# design.net
KiCad netlist of a schematic drawn in EasyEDA Pro
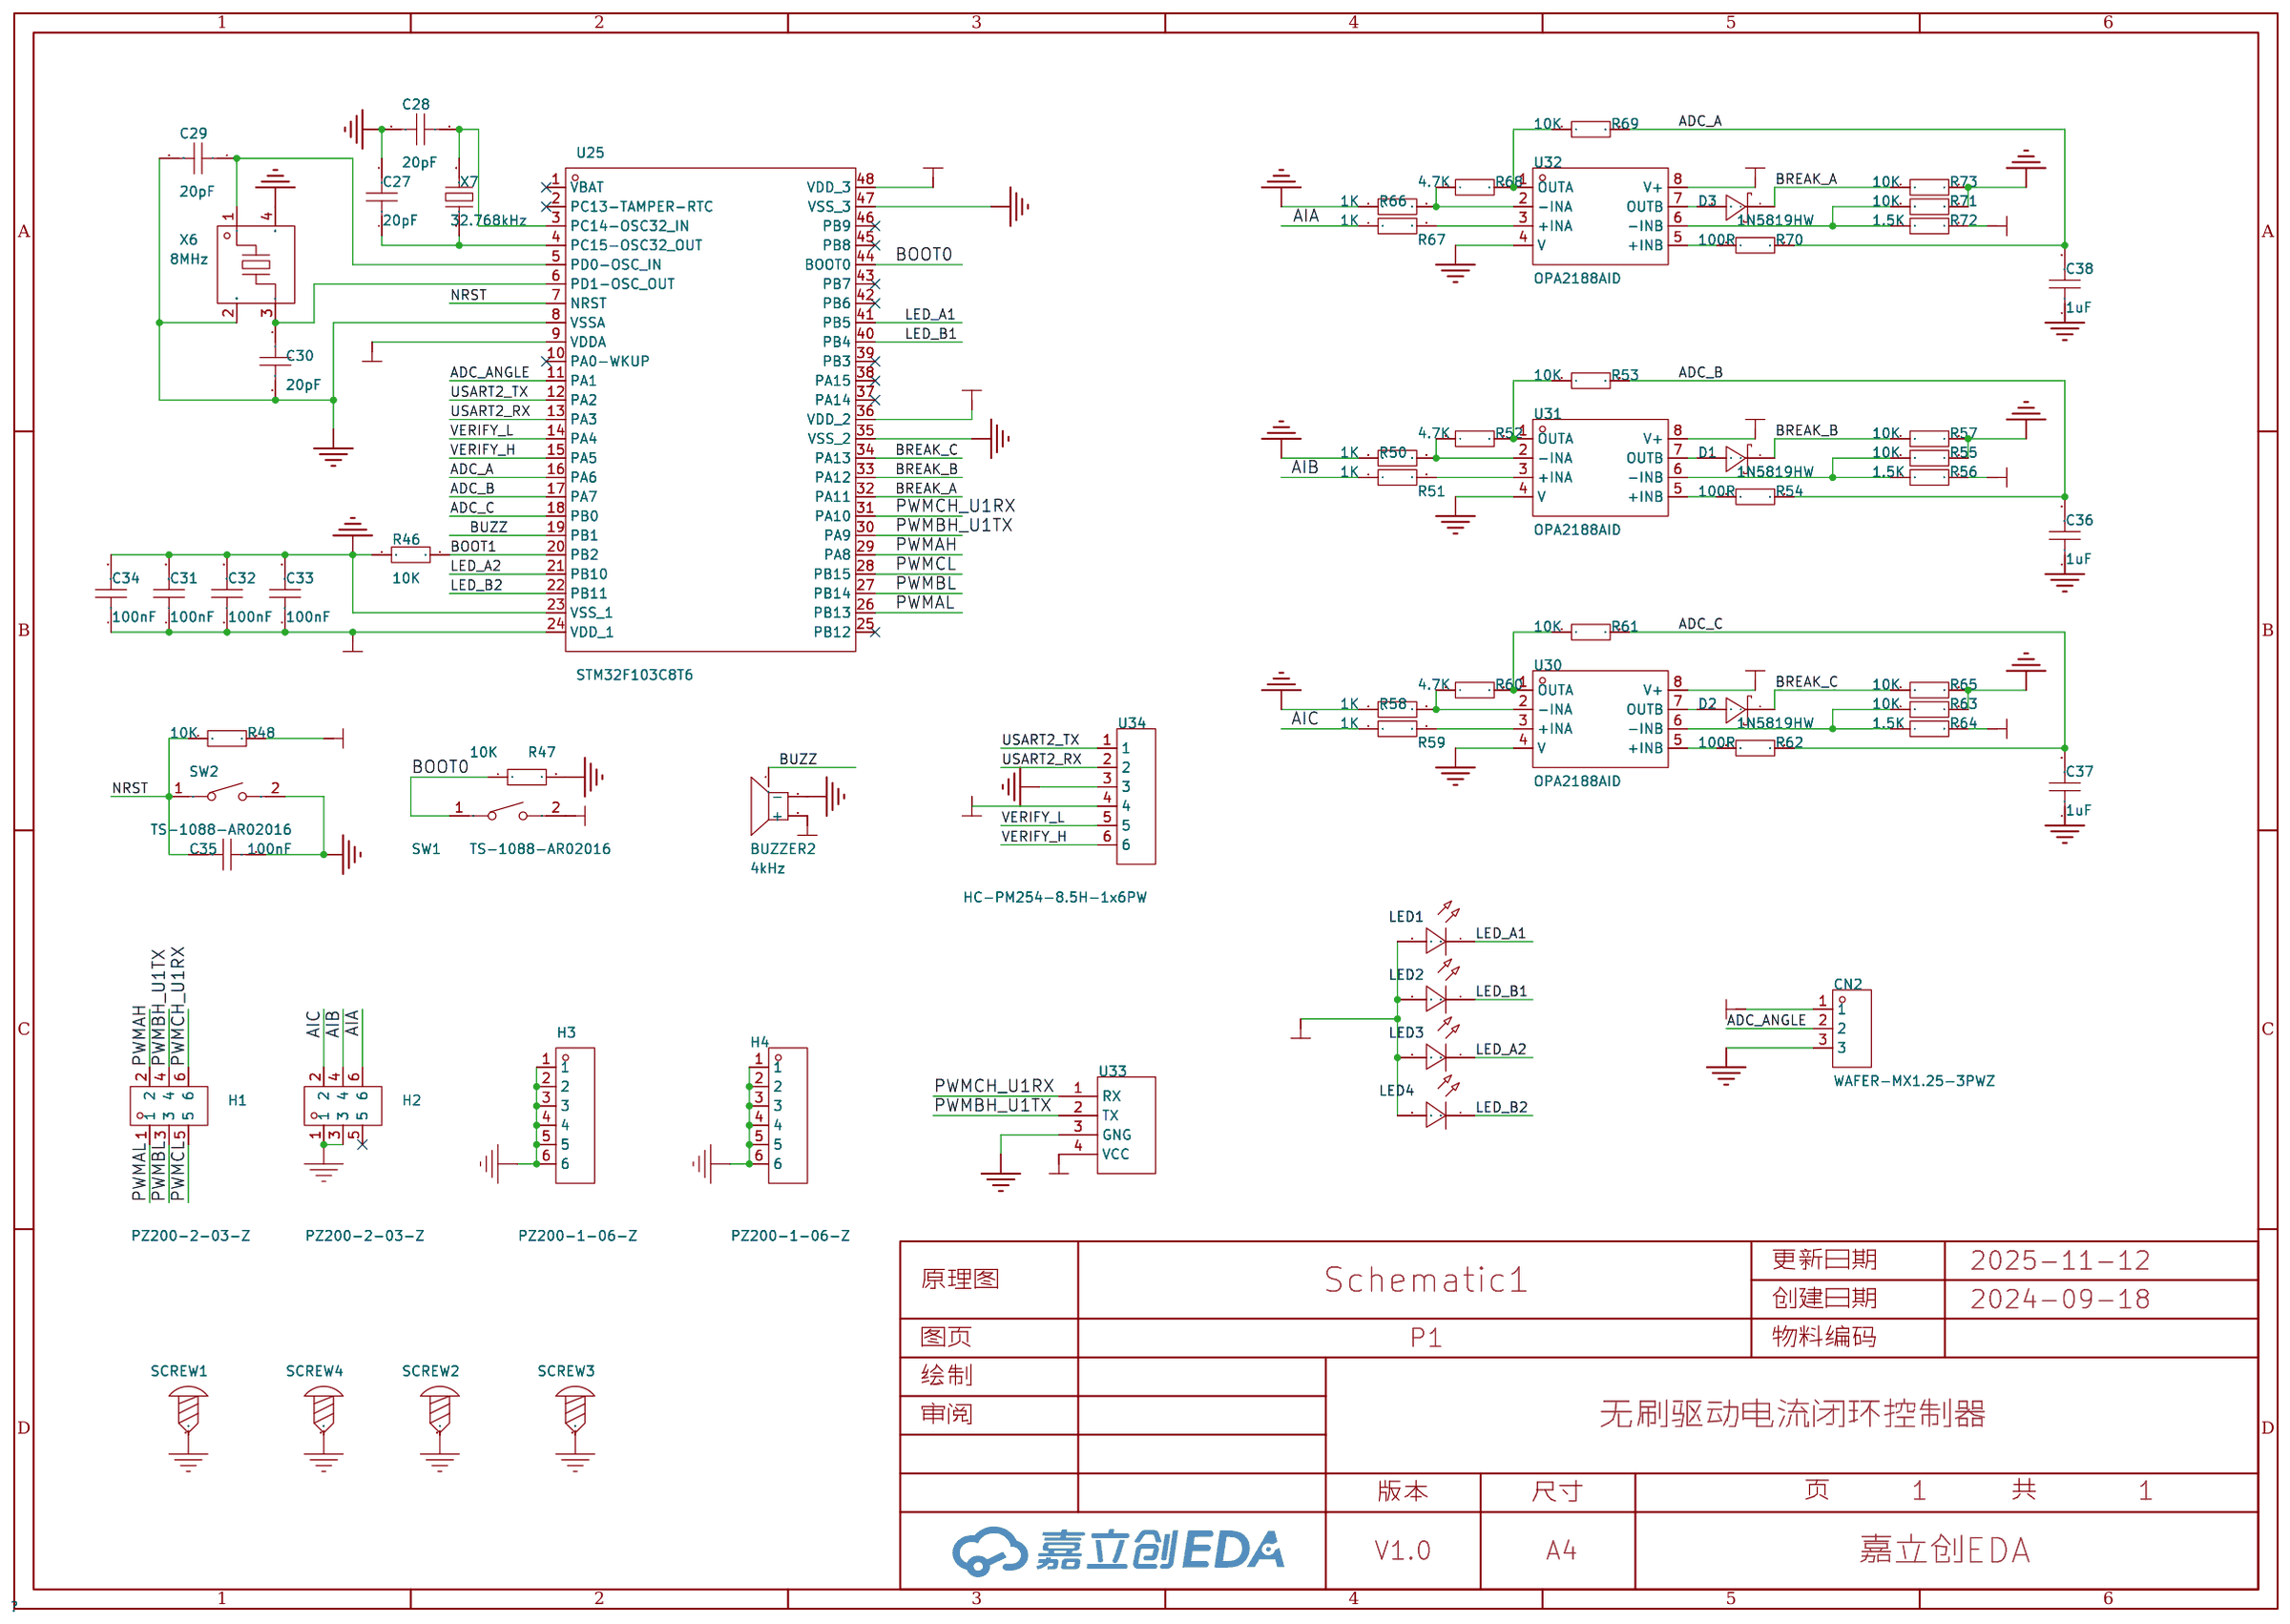
[diagram p0: schematic sheet]

(export (version "E")
  (design (tool "Eeschema 10.0.6"))
  (components
    (comp (ref "BUZZER2")
      (value "4kHz")
      (footprint "easyedapro:BUZ-SMD_L5.0-W5.5-P4.60")
      (description "驱动方式:无源(外部驱动);构造类型:电磁式;频率:4kHz;")
      (fields (field (name "Manufacturer Part") "MLT-5020") (field (name "Manufacturer") "华能"))
      (libsource (lib "easyedapro") (part "MLT-5020"))
    )
    (comp (ref "C27")
      (value "20pF")
      (footprint "easyedapro:C0402")
      (libsource (lib "easyedapro") (part "CapAcitance"))
    )
    (comp (ref "C28")
      (value "20pF")
      (footprint "easyedapro:C0402")
      (libsource (lib "easyedapro") (part "CapAcitance"))
    )
    (comp (ref "C29")
      (value "20pF")
      (footprint "easyedapro:C0402")
      (libsource (lib "easyedapro") (part "CapAcitance"))
    )
    (comp (ref "C30")
      (value "20pF")
      (footprint "easyedapro:C0402")
      (libsource (lib "easyedapro") (part "CapAcitance"))
    )
    (comp (ref "C31")
      (value "100nF")
      (footprint "easyedapro:C0402")
      (libsource (lib "easyedapro") (part "CapAcitance"))
    )
    (comp (ref "C32")
      (value "100nF")
      (footprint "easyedapro:C0402")
      (libsource (lib "easyedapro") (part "CapAcitance"))
    )
    (comp (ref "C33")
      (value "100nF")
      (footprint "easyedapro:C0402")
      (libsource (lib "easyedapro") (part "CapAcitance"))
    )
    (comp (ref "C34")
      (value "100nF")
      (footprint "easyedapro:C0402")
      (libsource (lib "easyedapro") (part "CapAcitance"))
    )
    (comp (ref "C35")
      (value "100nF")
      (footprint "easyedapro:C0402")
      (libsource (lib "easyedapro") (part "CapAcitance"))
    )
    (comp (ref "C36")
      (value "1uF")
      (footprint "easyedapro:C0402")
      (libsource (lib "easyedapro") (part "CapAcitance"))
    )
    (comp (ref "C37")
      (value "1uF")
      (footprint "easyedapro:C0402")
      (libsource (lib "easyedapro") (part "CapAcitance"))
    )
    (comp (ref "C38")
      (value "1uF")
      (footprint "easyedapro:C0402")
      (libsource (lib "easyedapro") (part "CapAcitance"))
    )
    (comp (ref "CN2")
      (value "WAFER-MX1.25-3PWZ")
      (footprint "easyedapro:CONN-TH_3P-P1.25_XUNPU_WAFER-MX1.25-3PWZ")
      (description "间距:1.25mm;插针结构:1x3P;排数:1;每排PIN数:3;公母:公型插针;安装方式:弯插;额定电流:1A;工作温度范围:-25°C~+85°C;")
      (fields (field (name "Manufacturer") "XUNPU(讯普)"))
      (libsource (lib "easyedapro") (part "WAFER-MX1.25-3PWZ"))
    )
    (comp (ref "D1")
      (value "1N5819HW")
      (footprint "easyedapro:SOD-123_L2.7-W1.6-LS3.7-RD")
      (description "正向压降(Vf):450mV@1A;直流反向耐压(Vr):40V;整流电流:1A;")
      (fields (field (name "Manufacturer") "DIODES(美台)"))
      (libsource (lib "easyedapro") (part "1N5819HW-7-F"))
    )
    (comp (ref "D2")
      (value "1N5819HW")
      (footprint "easyedapro:SOD-123_L2.7-W1.6-LS3.7-RD")
      (description "正向压降(Vf):450mV@1A;直流反向耐压(Vr):40V;整流电流:1A;")
      (fields (field (name "Manufacturer") "DIODES(美台)"))
      (libsource (lib "easyedapro") (part "1N5819HW-7-F"))
    )
    (comp (ref "D3")
      (value "1N5819HW")
      (footprint "easyedapro:SOD-123_L2.7-W1.6-LS3.7-RD")
      (description "正向压降(Vf):450mV@1A;直流反向耐压(Vr):40V;整流电流:1A;")
      (fields (field (name "Manufacturer") "DIODES(美台)"))
      (libsource (lib "easyedapro") (part "1N5819HW-7-F"))
    )
    (comp (ref "H1")
      (value "PZ200-2-03-Z")
      (footprint "easyedapro:HDR-TH_6P-P2.00-V-M-R2-C3-S2.00")
      (fields (field (name "Manufacturer") "HCTL(华灿天禄)"))
      (libsource (lib "easyedapro") (part "PZ200-2-03-Z"))
    )
    (comp (ref "H2")
      (value "PZ200-2-03-Z")
      (footprint "easyedapro:HDR-TH_6P-P2.00-V-M-R2-C3-S2.00")
      (fields (field (name "Manufacturer") "HCTL(华灿天禄)"))
      (libsource (lib "easyedapro") (part "PZ200-2-03-Z"))
    )
    (comp (ref "H3")
      (value "PZ200-1-06-Z")
      (footprint "easyedapro:HDR-TH_6P-P2.00-V-M")
      (fields (field (name "Manufacturer") "HCTL(华灿天禄)"))
      (libsource (lib "easyedapro") (part "PZ200-1-06-Z"))
    )
    (comp (ref "H4")
      (value "PZ200-1-06-Z")
      (footprint "easyedapro:HDR-TH_6P-P2.00-V-M")
      (fields (field (name "Manufacturer") "HCTL(华灿天禄)"))
      (libsource (lib "easyedapro") (part "PZ200-1-06-Z"))
    )
    (comp (ref "LED1")
      (value "~")
      (footprint "easyedapro:LED_0402")
      (libsource (lib "easyedapro") (part "LED_G"))
    )
    (comp (ref "LED2")
      (value "~")
      (footprint "easyedapro:LED_0402")
      (libsource (lib "easyedapro") (part "LED_G"))
    )
    (comp (ref "LED3")
      (value "~")
      (footprint "easyedapro:LED_0402")
      (libsource (lib "easyedapro") (part "LED_G"))
    )
    (comp (ref "LED4")
      (value "~")
      (footprint "easyedapro:LED_0402")
      (libsource (lib "easyedapro") (part "LED_G"))
    )
    (comp (ref "R46") (value "10K") (footprint "easyedapro:R0402") (libsource (lib "easyedapro") (part "电阻")))
    (comp (ref "R47") (value "10K") (footprint "easyedapro:R0402") (libsource (lib "easyedapro") (part "电阻")))
    (comp (ref "R48") (value "10K") (footprint "easyedapro:R0402") (libsource (lib "easyedapro") (part "电阻")))
    (comp (ref "R50") (value "1K") (footprint "easyedapro:R0402") (libsource (lib "easyedapro") (part "电阻")))
    (comp (ref "R51") (value "1K") (footprint "easyedapro:R0402") (libsource (lib "easyedapro") (part "电阻")))
    (comp (ref "R52")
      (value "4.7K")
      (footprint "easyedapro:R0402")
      (libsource (lib "easyedapro") (part "电阻"))
    )
    (comp (ref "R53") (value "10K") (footprint "easyedapro:R0402") (libsource (lib "easyedapro") (part "电阻")))
    (comp (ref "R54")
      (value "100R")
      (footprint "easyedapro:R0402")
      (libsource (lib "easyedapro") (part "电阻"))
    )
    (comp (ref "R55") (value "10K") (footprint "easyedapro:R0402") (libsource (lib "easyedapro") (part "电阻")))
    (comp (ref "R56")
      (value "1.5K")
      (footprint "easyedapro:R0402")
      (libsource (lib "easyedapro") (part "电阻"))
    )
    (comp (ref "R57") (value "10K") (footprint "easyedapro:R0402") (libsource (lib "easyedapro") (part "电阻")))
    (comp (ref "R58") (value "1K") (footprint "easyedapro:R0402") (libsource (lib "easyedapro") (part "电阻")))
    (comp (ref "R59") (value "1K") (footprint "easyedapro:R0402") (libsource (lib "easyedapro") (part "电阻")))
    (comp (ref "R60")
      (value "4.7K")
      (footprint "easyedapro:R0402")
      (libsource (lib "easyedapro") (part "电阻"))
    )
    (comp (ref "R61") (value "10K") (footprint "easyedapro:R0402") (libsource (lib "easyedapro") (part "电阻")))
    (comp (ref "R62")
      (value "100R")
      (footprint "easyedapro:R0402")
      (libsource (lib "easyedapro") (part "电阻"))
    )
    (comp (ref "R63") (value "10K") (footprint "easyedapro:R0402") (libsource (lib "easyedapro") (part "电阻")))
    (comp (ref "R64")
      (value "1.5K")
      (footprint "easyedapro:R0402")
      (libsource (lib "easyedapro") (part "电阻"))
    )
    (comp (ref "R65") (value "10K") (footprint "easyedapro:R0402") (libsource (lib "easyedapro") (part "电阻")))
    (comp (ref "R66") (value "1K") (footprint "easyedapro:R0402") (libsource (lib "easyedapro") (part "电阻")))
    (comp (ref "R67") (value "1K") (footprint "easyedapro:R0402") (libsource (lib "easyedapro") (part "电阻")))
    (comp (ref "R68")
      (value "4.7K")
      (footprint "easyedapro:R0402")
      (libsource (lib "easyedapro") (part "电阻"))
    )
    (comp (ref "R69") (value "10K") (footprint "easyedapro:R0402") (libsource (lib "easyedapro") (part "电阻")))
    (comp (ref "R70")
      (value "100R")
      (footprint "easyedapro:R0402")
      (libsource (lib "easyedapro") (part "电阻"))
    )
    (comp (ref "R71") (value "10K") (footprint "easyedapro:R0402") (libsource (lib "easyedapro") (part "电阻")))
    (comp (ref "R72")
      (value "1.5K")
      (footprint "easyedapro:R0402")
      (libsource (lib "easyedapro") (part "电阻"))
    )
    (comp (ref "R73") (value "10K") (footprint "easyedapro:R0402") (libsource (lib "easyedapro") (part "电阻")))
    (comp (ref "SCREW1")
      (value "~")
      (footprint "easyedapro:M3螺丝")
      (libsource (lib "easyedapro") (part "螺丝孔"))
    )
    (comp (ref "SCREW2")
      (value "~")
      (footprint "easyedapro:M3螺丝")
      (libsource (lib "easyedapro") (part "螺丝孔"))
    )
    (comp (ref "SCREW3")
      (value "~")
      (footprint "easyedapro:M3螺丝")
      (libsource (lib "easyedapro") (part "螺丝孔"))
    )
    (comp (ref "SCREW4")
      (value "~")
      (footprint "easyedapro:M3螺丝")
      (libsource (lib "easyedapro") (part "螺丝孔"))
    )
    (comp (ref "SW1")
      (value "TS-1088-AR02016")
      (footprint "easyedapro:SW-SMD_L3.9-W3.0-P4.45")
      (fields (field (name "Manufacturer") "XUNPU(讯普)"))
      (libsource (lib "easyedapro") (part "TS-1088-AR02016"))
    )
    (comp (ref "SW2")
      (value "TS-1088-AR02016")
      (footprint "easyedapro:SW-SMD_L3.9-W3.0-P4.45")
      (fields (field (name "Manufacturer") "XUNPU(讯普)"))
      (libsource (lib "easyedapro") (part "TS-1088-AR02016"))
    )
    (comp (ref "U25")
      (value "STM32F103C8T6")
      (footprint "easyedapro:LQFP-48_L7.0-W7.0-P0.50-LS9.0-BL")
      (description "CPU内核:ARM-M3;CPU最大主频:72MHz;应用领域:-;")
      (fields (field (name "Manufacturer") "ST(意法半导体)"))
      (libsource (lib "easyedapro") (part "STM32F103C8T6"))
    )
    (comp (ref "U30")
      (value "OPA2188AID")
      (footprint "easyedapro:SOIC-8_L4.9-W3.9-P1.27-LS6.0-BL")
      (description "放大器数:双路;增益带宽积(GBP):2MHz;输入偏置电流(Ib):160pA;输入失调电压(Vos):6uV;压摆率(SR):0.8V/us;带宽(-3db):-;轨到轨:-;")
      (fields (field (name "Manufacturer") "TI(德州仪器)"))
      (libsource (lib "easyedapro") (part "OPA2188AID"))
    )
    (comp (ref "U31")
      (value "OPA2188AID")
      (footprint "easyedapro:SOIC-8_L4.9-W3.9-P1.27-LS6.0-BL")
      (description "放大器数:双路;增益带宽积(GBP):2MHz;输入偏置电流(Ib):160pA;输入失调电压(Vos):6uV;压摆率(SR):0.8V/us;带宽(-3db):-;轨到轨:-;")
      (fields (field (name "Manufacturer") "TI(德州仪器)"))
      (libsource (lib "easyedapro") (part "OPA2188AID"))
    )
    (comp (ref "U32")
      (value "OPA2188AID")
      (footprint "easyedapro:SOIC-8_L4.9-W3.9-P1.27-LS6.0-BL")
      (description "放大器数:双路;增益带宽积(GBP):2MHz;输入偏置电流(Ib):160pA;输入失调电压(Vos):6uV;压摆率(SR):0.8V/us;带宽(-3db):-;轨到轨:-;")
      (fields (field (name "Manufacturer") "TI(德州仪器)"))
      (libsource (lib "easyedapro") (part "OPA2188AID"))
    )
    (comp (ref "U33")
      (value "~")
      (footprint "easyedapro:2.54串口烧录接口")
      (libsource (lib "easyedapro") (part "2.54串口烧录接口"))
    )
    (comp (ref "U34")
      (value "HC-PM254-8.5H-1x6PW")
      (footprint "easyedapro:HDR-TH_HC-PM254-8.5H-1X6PW")
      (fields (field (name "Manufacturer") "HC(虹成电子)"))
      (libsource (lib "easyedapro") (part "HC-PM254-8.5H-1X6PW"))
    )
    (comp (ref "X6")
      (value "8MHz")
      (footprint "easyedapro:OSC-SMD_4P-L3.2-W2.5-BL")
      (description "晶振类型:贴片无源晶振;频率:8MHz;常温频差:±10ppm;负载电容:12pF;频率稳定度(全温):±30ppm;")
      (fields (field (name "Manufacturer Part") "X32258MOB4SI") (field (name "Manufacturer") "YXC(扬兴晶振)"))
      (libsource (lib "easyedapro") (part "X32258MOB4SI"))
    )
    (comp (ref "X7")
      (value "32.768kHz")
      (footprint "easyedapro:OSC-SMD_L3.2-W1.5")
      (description "频率:32.768kHz;负载电容:12.5pF;频率公差:±20ppm;")
      (fields (field (name "Manufacturer Part") "X321532768KGD2SI") (field (name "Manufacturer") "YXC(扬兴晶振)"))
      (libsource (lib "easyedapro") (part "X321532768KGD2SI"))
    )
  )
  (nets
    (net (code "1") (name "/ADC_A") (class "Default")
      (node (ref "C38") (pin "2") (pinfunction "2_2") (pintype "input"))
      (node (ref "R69") (pin "2") (pinfunction "2_2") (pintype "input"))
      (node (ref "R70") (pin "2") (pinfunction "2_2") (pintype "input"))
      (node (ref "U25") (pin "16") (pinfunction "PA6_16") (pintype "unspecified"))
    )
    (net (code "2") (name "/ADC_ANGLE") (class "Default")
      (node (ref "CN2") (pin "2") (pinfunction "2_2") (pintype "input"))
      (node (ref "U25") (pin "11") (pinfunction "PA1_11") (pintype "unspecified"))
    )
    (net (code "3") (name "/ADC_B") (class "Default")
      (node (ref "C36") (pin "2") (pinfunction "2_2") (pintype "input"))
      (node (ref "R53") (pin "2") (pinfunction "2_2") (pintype "input"))
      (node (ref "R54") (pin "2") (pinfunction "2_2") (pintype "input"))
      (node (ref "U25") (pin "17") (pinfunction "PA7_17") (pintype "unspecified"))
    )
    (net (code "4") (name "/ADC_C") (class "Default")
      (node (ref "C37") (pin "2") (pinfunction "2_2") (pintype "input"))
      (node (ref "R61") (pin "2") (pinfunction "2_2") (pintype "input"))
      (node (ref "R62") (pin "2") (pinfunction "2_2") (pintype "input"))
      (node (ref "U25") (pin "18") (pinfunction "PB0_18") (pintype "unspecified"))
    )
    (net (code "5") (name "/AIA") (class "Default")
      (node (ref "H2") (pin "6") (pinfunction "6_6") (pintype "unspecified"))
      (node (ref "R67") (pin "1") (pinfunction "1_1") (pintype "input"))
    )
    (net (code "6") (name "/AIB") (class "Default")
      (node (ref "H2") (pin "4") (pinfunction "4_4") (pintype "unspecified"))
      (node (ref "R51") (pin "1") (pinfunction "1_1") (pintype "input"))
    )
    (net (code "7") (name "/AIC") (class "Default")
      (node (ref "H2") (pin "2") (pinfunction "2_2") (pintype "unspecified"))
      (node (ref "R59") (pin "1") (pinfunction "1_1") (pintype "input"))
    )
    (net (code "8") (name "/BOOT0") (class "Default")
      (node (ref "R47") (pin "1") (pinfunction "1_1") (pintype "input"))
      (node (ref "SW1") (pin "1") (pinfunction "1_1") (pintype "unspecified"))
      (node (ref "U25") (pin "44") (pinfunction "BOOT0_44") (pintype "unspecified"))
    )
    (net (code "9") (name "/BOOT1") (class "Default")
      (node (ref "R46") (pin "1") (pinfunction "1_1") (pintype "input"))
      (node (ref "U25") (pin "20") (pinfunction "PB2_20") (pintype "unspecified"))
    )
    (net (code "10") (name "/BREAK_A") (class "Default")
      (node (ref "D3") (pin "1") (pinfunction "K_1") (pintype "unspecified"))
      (node (ref "R73") (pin "1") (pinfunction "1_1") (pintype "input"))
      (node (ref "U25") (pin "32") (pinfunction "PA11_32") (pintype "unspecified"))
    )
    (net (code "11") (name "/BREAK_B") (class "Default")
      (node (ref "D1") (pin "1") (pinfunction "K_1") (pintype "unspecified"))
      (node (ref "R57") (pin "1") (pinfunction "1_1") (pintype "input"))
      (node (ref "U25") (pin "33") (pinfunction "PA12_33") (pintype "unspecified"))
    )
    (net (code "12") (name "/BREAK_C") (class "Default")
      (node (ref "D2") (pin "1") (pinfunction "K_1") (pintype "unspecified"))
      (node (ref "R65") (pin "1") (pinfunction "1_1") (pintype "input"))
      (node (ref "U25") (pin "34") (pinfunction "PA13_34") (pintype "unspecified"))
    )
    (net (code "13") (name "/BUZZ") (class "Default")
      (node (ref "BUZZER2") (pin "3") (pinfunction "NC_3") (pintype "unspecified"))
      (node (ref "U25") (pin "19") (pinfunction "PB1_19") (pintype "unspecified"))
    )
    (net (code "14") (name "/LED_A1") (class "Default")
      (node (ref "LED1") (pin "1") (pinfunction "C_1") (pintype "input"))
      (node (ref "U25") (pin "41") (pinfunction "PB5_41") (pintype "unspecified"))
    )
    (net (code "15") (name "/LED_A2") (class "Default")
      (node (ref "LED3") (pin "1") (pinfunction "C_1") (pintype "input"))
      (node (ref "U25") (pin "21") (pinfunction "PB10_21") (pintype "unspecified"))
    )
    (net (code "16") (name "/LED_B1") (class "Default")
      (node (ref "LED2") (pin "1") (pinfunction "C_1") (pintype "input"))
      (node (ref "U25") (pin "40") (pinfunction "PB4_40") (pintype "unspecified"))
    )
    (net (code "17") (name "/LED_B2") (class "Default")
      (node (ref "LED4") (pin "1") (pinfunction "C_1") (pintype "input"))
      (node (ref "U25") (pin "22") (pinfunction "PB11_22") (pintype "unspecified"))
    )
    (net (code "18") (name "/NRST") (class "Default")
      (node (ref "C35") (pin "1") (pinfunction "1_1") (pintype "input"))
      (node (ref "R48") (pin "1") (pinfunction "1_1") (pintype "input"))
      (node (ref "SW2") (pin "1") (pinfunction "1_1") (pintype "unspecified"))
      (node (ref "U25") (pin "7") (pinfunction "NRST_7") (pintype "unspecified"))
    )
    (net (code "19") (name "/PWMAH") (class "Default")
      (node (ref "H1") (pin "2") (pinfunction "2_2") (pintype "unspecified"))
      (node (ref "U25") (pin "29") (pinfunction "PA8_29") (pintype "unspecified"))
    )
    (net (code "20") (name "/PWMAL") (class "Default")
      (node (ref "H1") (pin "1") (pinfunction "1_1") (pintype "unspecified"))
      (node (ref "U25") (pin "26") (pinfunction "PB13_26") (pintype "unspecified"))
    )
    (net (code "21") (name "/PWMBH_U1TX") (class "Default")
      (node (ref "H1") (pin "4") (pinfunction "4_4") (pintype "unspecified"))
      (node (ref "U25") (pin "30") (pinfunction "PA9_30") (pintype "unspecified"))
      (node (ref "U33") (pin "2") (pinfunction "TX_2") (pintype "input"))
    )
    (net (code "22") (name "/PWMBL") (class "Default")
      (node (ref "H1") (pin "3") (pinfunction "3_3") (pintype "unspecified"))
      (node (ref "U25") (pin "27") (pinfunction "PB14_27") (pintype "unspecified"))
    )
    (net (code "23") (name "/PWMCH_U1RX") (class "Default")
      (node (ref "H1") (pin "6") (pinfunction "6_6") (pintype "unspecified"))
      (node (ref "U25") (pin "31") (pinfunction "PA10_31") (pintype "unspecified"))
      (node (ref "U33") (pin "1") (pinfunction "RX_1") (pintype "input"))
    )
    (net (code "24") (name "/PWMCL") (class "Default")
      (node (ref "H1") (pin "5") (pinfunction "5_5") (pintype "unspecified"))
      (node (ref "U25") (pin "28") (pinfunction "PB15_28") (pintype "unspecified"))
    )
    (net (code "25") (name "/USART2_RX") (class "Default")
      (node (ref "U25") (pin "13") (pinfunction "PA3_13") (pintype "unspecified"))
      (node (ref "U34") (pin "2") (pinfunction "2_2") (pintype "unspecified"))
    )
    (net (code "26") (name "/USART2_TX") (class "Default")
      (node (ref "U25") (pin "12") (pinfunction "PA2_12") (pintype "unspecified"))
      (node (ref "U34") (pin "1") (pinfunction "1_1") (pintype "unspecified"))
    )
    (net (code "27") (name "/VERIFY_H") (class "Default")
      (node (ref "U25") (pin "15") (pinfunction "PA5_15") (pintype "unspecified"))
      (node (ref "U34") (pin "6") (pinfunction "6_6") (pintype "unspecified"))
    )
    (net (code "28") (name "/VERIFY_L") (class "Default")
      (node (ref "U25") (pin "14") (pinfunction "PA4_14") (pintype "unspecified"))
      (node (ref "U34") (pin "5") (pinfunction "5_5") (pintype "unspecified"))
    )
    (net (code "29") (name "3V3") (class "Default")
      (node (ref "BUZZER2") (pin "1") (pinfunction "+_1") (pintype "unspecified"))
      (node (ref "C31") (pin "1") (pinfunction "1_1") (pintype "input"))
      (node (ref "C32") (pin "1") (pinfunction "1_1") (pintype "input"))
      (node (ref "C33") (pin "1") (pinfunction "1_1") (pintype "input"))
      (node (ref "C34") (pin "1") (pinfunction "1_1") (pintype "input"))
      (node (ref "CN2") (pin "1") (pinfunction "1_1") (pintype "input"))
      (node (ref "LED1") (pin "2") (pinfunction "A_2") (pintype "input"))
      (node (ref "LED2") (pin "2") (pinfunction "A_2") (pintype "input"))
      (node (ref "LED3") (pin "2") (pinfunction "A_2") (pintype "input"))
      (node (ref "LED4") (pin "2") (pinfunction "A_2") (pintype "input"))
      (node (ref "R48") (pin "2") (pinfunction "2_2") (pintype "input"))
      (node (ref "R56") (pin "2") (pinfunction "2_2") (pintype "input"))
      (node (ref "R64") (pin "2") (pinfunction "2_2") (pintype "input"))
      (node (ref "R72") (pin "2") (pinfunction "2_2") (pintype "input"))
      (node (ref "SW1") (pin "2") (pinfunction "2_2") (pintype "unspecified"))
      (node (ref "U25") (pin "24") (pinfunction "VDD_1_24") (pintype "unspecified"))
      (node (ref "U25") (pin "36") (pinfunction "VDD_2_36") (pintype "unspecified"))
      (node (ref "U25") (pin "48") (pinfunction "VDD_3_48") (pintype "unspecified"))
      (node (ref "U25") (pin "9") (pinfunction "VDDA_9") (pintype "unspecified"))
      (node (ref "U30") (pin "8") (pinfunction "V+_8") (pintype "unspecified"))
      (node (ref "U31") (pin "8") (pinfunction "V+_8") (pintype "unspecified"))
      (node (ref "U32") (pin "8") (pinfunction "V+_8") (pintype "unspecified"))
      (node (ref "U33") (pin "4") (pinfunction "VCC_4") (pintype "input"))
      (node (ref "U34") (pin "4") (pinfunction "4_4") (pintype "unspecified"))
    )
    (net (code "30") (name "GND") (class "Default")
      (node (ref "BUZZER2") (pin "2") (pinfunction "-_2") (pintype "unspecified"))
      (node (ref "C27") (pin "2") (pinfunction "2_2") (pintype "input"))
      (node (ref "C28") (pin "2") (pinfunction "2_2") (pintype "input"))
      (node (ref "C29") (pin "2") (pinfunction "2_2") (pintype "input"))
      (node (ref "C30") (pin "2") (pinfunction "2_2") (pintype "input"))
      (node (ref "C31") (pin "2") (pinfunction "2_2") (pintype "input"))
      (node (ref "C32") (pin "2") (pinfunction "2_2") (pintype "input"))
      (node (ref "C33") (pin "2") (pinfunction "2_2") (pintype "input"))
      (node (ref "C34") (pin "2") (pinfunction "2_2") (pintype "input"))
      (node (ref "C35") (pin "2") (pinfunction "2_2") (pintype "input"))
      (node (ref "C36") (pin "1") (pinfunction "1_1") (pintype "input"))
      (node (ref "C37") (pin "1") (pinfunction "1_1") (pintype "input"))
      (node (ref "C38") (pin "1") (pinfunction "1_1") (pintype "input"))
      (node (ref "CN2") (pin "3") (pinfunction "3_3") (pintype "input"))
      (node (ref "H2") (pin "1") (pinfunction "1_1") (pintype "unspecified"))
      (node (ref "H2") (pin "3") (pinfunction "3_3") (pintype "unspecified"))
      (node (ref "H3") (pin "1") (pinfunction "1_1") (pintype "unspecified"))
      (node (ref "H3") (pin "2") (pinfunction "2_2") (pintype "unspecified"))
      (node (ref "H3") (pin "3") (pinfunction "3_3") (pintype "unspecified"))
      (node (ref "H3") (pin "4") (pinfunction "4_4") (pintype "unspecified"))
      (node (ref "H3") (pin "5") (pinfunction "5_5") (pintype "unspecified"))
      (node (ref "H3") (pin "6") (pinfunction "6_6") (pintype "unspecified"))
      (node (ref "H4") (pin "1") (pinfunction "1_1") (pintype "unspecified"))
      (node (ref "H4") (pin "2") (pinfunction "2_2") (pintype "unspecified"))
      (node (ref "H4") (pin "3") (pinfunction "3_3") (pintype "unspecified"))
      (node (ref "H4") (pin "4") (pinfunction "4_4") (pintype "unspecified"))
      (node (ref "H4") (pin "5") (pinfunction "5_5") (pintype "unspecified"))
      (node (ref "H4") (pin "6") (pinfunction "6_6") (pintype "unspecified"))
      (node (ref "R46") (pin "2") (pinfunction "2_2") (pintype "input"))
      (node (ref "R47") (pin "2") (pinfunction "2_2") (pintype "input"))
      (node (ref "R50") (pin "1") (pinfunction "1_1") (pintype "input"))
      (node (ref "R55") (pin "2") (pinfunction "2_2") (pintype "input"))
      (node (ref "R57") (pin "2") (pinfunction "2_2") (pintype "input"))
      (node (ref "R58") (pin "1") (pinfunction "1_1") (pintype "input"))
      (node (ref "R63") (pin "2") (pinfunction "2_2") (pintype "input"))
      (node (ref "R65") (pin "2") (pinfunction "2_2") (pintype "input"))
      (node (ref "R66") (pin "1") (pinfunction "1_1") (pintype "input"))
      (node (ref "R71") (pin "2") (pinfunction "2_2") (pintype "input"))
      (node (ref "R73") (pin "2") (pinfunction "2_2") (pintype "input"))
      (node (ref "SCREW1") (pin "1") (pinfunction "1_1") (pintype "input"))
      (node (ref "SCREW2") (pin "1") (pinfunction "1_1") (pintype "input"))
      (node (ref "SCREW3") (pin "1") (pinfunction "1_1") (pintype "input"))
      (node (ref "SCREW4") (pin "1") (pinfunction "1_1") (pintype "input"))
      (node (ref "SW2") (pin "2") (pinfunction "2_2") (pintype "unspecified"))
      (node (ref "U25") (pin "23") (pinfunction "VSS_1_23") (pintype "unspecified"))
      (node (ref "U25") (pin "35") (pinfunction "VSS_2_35") (pintype "unspecified"))
      (node (ref "U25") (pin "47") (pinfunction "VSS_3_47") (pintype "unspecified"))
      (node (ref "U25") (pin "8") (pinfunction "VSSA_8") (pintype "unspecified"))
      (node (ref "U30") (pin "4") (pinfunction "V_4") (pintype "unspecified"))
      (node (ref "U31") (pin "4") (pinfunction "V_4") (pintype "unspecified"))
      (node (ref "U32") (pin "4") (pinfunction "V_4") (pintype "unspecified"))
      (node (ref "U33") (pin "3") (pinfunction "GNG_3") (pintype "input"))
      (node (ref "U34") (pin "3") (pinfunction "3_3") (pintype "unspecified"))
      (node (ref "X6") (pin "2") (pinfunction "GND_2") (pintype "input"))
      (node (ref "X6") (pin "4") (pinfunction "GND_4") (pintype "input"))
    )
    (net (code "31") (name "Net-(D1-A)") (class "Default")
      (node (ref "D1") (pin "2") (pinfunction "A_2") (pintype "unspecified"))
      (node (ref "U31") (pin "7") (pinfunction "OUTB_7") (pintype "unspecified"))
    )
    (net (code "32") (name "Net-(D2-A)") (class "Default")
      (node (ref "D2") (pin "2") (pinfunction "A_2") (pintype "unspecified"))
      (node (ref "U30") (pin "7") (pinfunction "OUTB_7") (pintype "unspecified"))
    )
    (net (code "33") (name "Net-(D3-A)") (class "Default")
      (node (ref "D3") (pin "2") (pinfunction "A_2") (pintype "unspecified"))
      (node (ref "U32") (pin "7") (pinfunction "OUTB_7") (pintype "unspecified"))
    )
    (net (code "34") (name "Net-(U25-PC14-OSC32_IN)") (class "Default")
      (node (ref "C28") (pin "1") (pinfunction "1_1") (pintype "input"))
      (node (ref "U25") (pin "3") (pinfunction "PC14-OSC32_IN_3") (pintype "unspecified"))
      (node (ref "X7") (pin "2") (pinfunction "2_2") (pintype "input"))
    )
    (net (code "35") (name "Net-(U25-PC15-OSC32_OUT)") (class "Default")
      (node (ref "C27") (pin "1") (pinfunction "1_1") (pintype "input"))
      (node (ref "U25") (pin "4") (pinfunction "PC15-OSC32_OUT_4") (pintype "unspecified"))
      (node (ref "X7") (pin "1") (pinfunction "1_1") (pintype "input"))
    )
    (net (code "36") (name "Net-(U25-PD0-OSC_IN)") (class "Default")
      (node (ref "C29") (pin "1") (pinfunction "1_1") (pintype "input"))
      (node (ref "U25") (pin "5") (pinfunction "PD0-OSC_IN_5") (pintype "unspecified"))
      (node (ref "X6") (pin "1") (pinfunction "1_1") (pintype "input"))
    )
    (net (code "37") (name "Net-(U25-PD1-OSC_OUT)") (class "Default")
      (node (ref "C30") (pin "1") (pinfunction "1_1") (pintype "input"))
      (node (ref "U25") (pin "6") (pinfunction "PD1-OSC_OUT_6") (pintype "unspecified"))
      (node (ref "X6") (pin "3") (pinfunction "3_3") (pintype "input"))
    )
    (net (code "38") (name "Net-(U30-+INA)") (class "Default")
      (node (ref "R59") (pin "2") (pinfunction "2_2") (pintype "input"))
      (node (ref "U30") (pin "3") (pinfunction "+INA_3") (pintype "unspecified"))
    )
    (net (code "39") (name "Net-(U30-+INB)") (class "Default")
      (node (ref "R62") (pin "1") (pinfunction "1_1") (pintype "input"))
      (node (ref "U30") (pin "5") (pinfunction "+INB_5") (pintype "unspecified"))
    )
    (net (code "40") (name "Net-(U30--INA)") (class "Default")
      (node (ref "R58") (pin "2") (pinfunction "2_2") (pintype "input"))
      (node (ref "R60") (pin "1") (pinfunction "1_1") (pintype "input"))
      (node (ref "U30") (pin "2") (pinfunction "-INA_2") (pintype "unspecified"))
    )
    (net (code "41") (name "Net-(U30--INB)") (class "Default")
      (node (ref "R63") (pin "1") (pinfunction "1_1") (pintype "input"))
      (node (ref "R64") (pin "1") (pinfunction "1_1") (pintype "input"))
      (node (ref "U30") (pin "6") (pinfunction "-INB_6") (pintype "unspecified"))
    )
    (net (code "42") (name "Net-(U30-OUTA)") (class "Default")
      (node (ref "R60") (pin "2") (pinfunction "2_2") (pintype "input"))
      (node (ref "R61") (pin "1") (pinfunction "1_1") (pintype "input"))
      (node (ref "U30") (pin "1") (pinfunction "OUTA_1") (pintype "unspecified"))
    )
    (net (code "43") (name "Net-(U31-+INA)") (class "Default")
      (node (ref "R51") (pin "2") (pinfunction "2_2") (pintype "input"))
      (node (ref "U31") (pin "3") (pinfunction "+INA_3") (pintype "unspecified"))
    )
    (net (code "44") (name "Net-(U31-+INB)") (class "Default")
      (node (ref "R54") (pin "1") (pinfunction "1_1") (pintype "input"))
      (node (ref "U31") (pin "5") (pinfunction "+INB_5") (pintype "unspecified"))
    )
    (net (code "45") (name "Net-(U31--INA)") (class "Default")
      (node (ref "R50") (pin "2") (pinfunction "2_2") (pintype "input"))
      (node (ref "R52") (pin "1") (pinfunction "1_1") (pintype "input"))
      (node (ref "U31") (pin "2") (pinfunction "-INA_2") (pintype "unspecified"))
    )
    (net (code "46") (name "Net-(U31--INB)") (class "Default")
      (node (ref "R55") (pin "1") (pinfunction "1_1") (pintype "input"))
      (node (ref "R56") (pin "1") (pinfunction "1_1") (pintype "input"))
      (node (ref "U31") (pin "6") (pinfunction "-INB_6") (pintype "unspecified"))
    )
    (net (code "47") (name "Net-(U31-OUTA)") (class "Default")
      (node (ref "R52") (pin "2") (pinfunction "2_2") (pintype "input"))
      (node (ref "R53") (pin "1") (pinfunction "1_1") (pintype "input"))
      (node (ref "U31") (pin "1") (pinfunction "OUTA_1") (pintype "unspecified"))
    )
    (net (code "48") (name "Net-(U32-+INA)") (class "Default")
      (node (ref "R67") (pin "2") (pinfunction "2_2") (pintype "input"))
      (node (ref "U32") (pin "3") (pinfunction "+INA_3") (pintype "unspecified"))
    )
    (net (code "49") (name "Net-(U32-+INB)") (class "Default")
      (node (ref "R70") (pin "1") (pinfunction "1_1") (pintype "input"))
      (node (ref "U32") (pin "5") (pinfunction "+INB_5") (pintype "unspecified"))
    )
    (net (code "50") (name "Net-(U32--INA)") (class "Default")
      (node (ref "R66") (pin "2") (pinfunction "2_2") (pintype "input"))
      (node (ref "R68") (pin "1") (pinfunction "1_1") (pintype "input"))
      (node (ref "U32") (pin "2") (pinfunction "-INA_2") (pintype "unspecified"))
    )
    (net (code "51") (name "Net-(U32--INB)") (class "Default")
      (node (ref "R71") (pin "1") (pinfunction "1_1") (pintype "input"))
      (node (ref "R72") (pin "1") (pinfunction "1_1") (pintype "input"))
      (node (ref "U32") (pin "6") (pinfunction "-INB_6") (pintype "unspecified"))
    )
    (net (code "52") (name "Net-(U32-OUTA)") (class "Default")
      (node (ref "R68") (pin "2") (pinfunction "2_2") (pintype "input"))
      (node (ref "R69") (pin "1") (pinfunction "1_1") (pintype "input"))
      (node (ref "U32") (pin "1") (pinfunction "OUTA_1") (pintype "unspecified"))
    )
    (net (code "53") (name "unconnected-(H2-Pad5)") (class "Default")
      (node (ref "H2") (pin "5") (pinfunction "5_5") (pintype "unspecified+no_connect"))
    )
    (net (code "54") (name "unconnected-(U25-PA0-WKUP-Pad10)") (class "Default")
      (node (ref "U25") (pin "10") (pinfunction "PA0-WKUP_10") (pintype "unspecified+no_connect"))
    )
    (net (code "55") (name "unconnected-(U25-PA14-Pad37)") (class "Default")
      (node (ref "U25") (pin "37") (pinfunction "PA14_37") (pintype "unspecified+no_connect"))
    )
    (net (code "56") (name "unconnected-(U25-PA15-Pad38)") (class "Default")
      (node (ref "U25") (pin "38") (pinfunction "PA15_38") (pintype "unspecified+no_connect"))
    )
    (net (code "57") (name "unconnected-(U25-PB3-Pad39)") (class "Default")
      (node (ref "U25") (pin "39") (pinfunction "PB3_39") (pintype "unspecified+no_connect"))
    )
    (net (code "58") (name "unconnected-(U25-PB6-Pad42)") (class "Default")
      (node (ref "U25") (pin "42") (pinfunction "PB6_42") (pintype "unspecified+no_connect"))
    )
    (net (code "59") (name "unconnected-(U25-PB7-Pad43)") (class "Default")
      (node (ref "U25") (pin "43") (pinfunction "PB7_43") (pintype "unspecified+no_connect"))
    )
    (net (code "60") (name "unconnected-(U25-PB8-Pad45)") (class "Default")
      (node (ref "U25") (pin "45") (pinfunction "PB8_45") (pintype "unspecified+no_connect"))
    )
    (net (code "61") (name "unconnected-(U25-PB9-Pad46)") (class "Default")
      (node (ref "U25") (pin "46") (pinfunction "PB9_46") (pintype "unspecified+no_connect"))
    )
    (net (code "62") (name "unconnected-(U25-PB12-Pad25)") (class "Default")
      (node (ref "U25") (pin "25") (pinfunction "PB12_25") (pintype "unspecified+no_connect"))
    )
    (net (code "63") (name "unconnected-(U25-PC13-TAMPER-RTC-Pad2)") (class "Default")
      (node (ref "U25") (pin "2") (pinfunction "PC13-TAMPER-RTC_2") (pintype "unspecified+no_connect"))
    )
    (net (code "64") (name "unconnected-(U25-VBAT-Pad1)") (class "Default")
      (node (ref "U25") (pin "1") (pinfunction "VBAT_1") (pintype "unspecified+no_connect"))
    )
  )
)
